# Project_Milestone04_v3_0_0.net
KiCad netlist of a schematic drawn in EAGLE
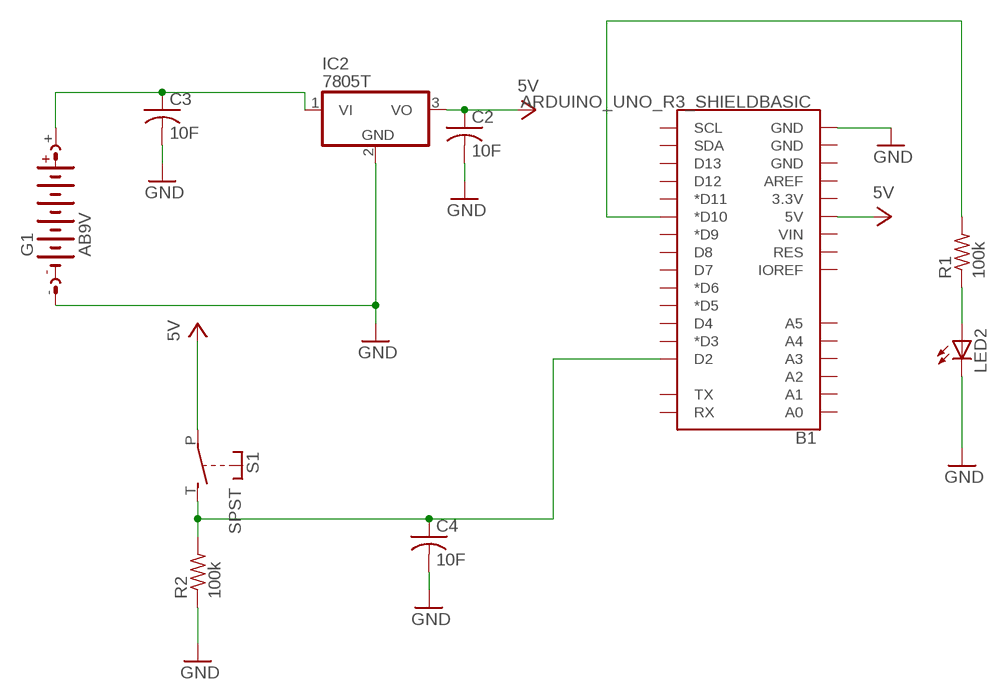
[diagram p0: schematic, sheet 1]

(export (version "E")
  (design (tool "Eeschema 10.0.6"))
  (components
    (comp (ref "B1")
      (value "ARDUINO_UNO_R3_SHIELDBASIC")
      (footprint "eagle-import:UNO_R3_SHIELD")
      (libsource (lib "eagle-import") (part "ARDUINO_UNO_R3_SHIELDBASIC"))
    )
    (comp (ref "C2")
      (value "10F")
      (footprint "eagle-import:C0805")
      (libsource (lib "eagle-import") (part "C-USC0805"))
    )
    (comp (ref "C3")
      (value "10F")
      (footprint "eagle-import:C0805")
      (libsource (lib "eagle-import") (part "C-USC0805"))
    )
    (comp (ref "C4")
      (value "10F")
      (footprint "eagle-import:C0805")
      (libsource (lib "eagle-import") (part "C-USC0805"))
    )
    (comp (ref "G1")
      (value "AB9V")
      (footprint "eagle-import:AB9V")
      (libsource (lib "eagle-import") (part "AB9V"))
    )
    (comp (ref "IC2")
      (value "7805T")
      (footprint "eagle-import:TO220H")
      (libsource (lib "eagle-import") (part "78T05"))
    )
    (comp (ref "LED2")
      (value "LED5MM")
      (footprint "eagle-import:LED5MM")
      (libsource (lib "eagle-import") (part "LED5MM"))
    )
    (comp (ref "R1")
      (value "100k")
      (footprint "eagle-import:0207_10")
      (libsource (lib "eagle-import") (part "R-US_0207/10"))
    )
    (comp (ref "R2")
      (value "100k")
      (footprint "eagle-import:0207_10")
      (libsource (lib "eagle-import") (part "R-US_0207/10"))
    )
    (comp (ref "S1")
      (value "SPST")
      (footprint "eagle-import:JUDCOSPST")
      (libsource (lib "eagle-import") (part "SPST"))
    )
  )
  (nets
    (net (code "1") (name "5V") (class "Default")
      (node (ref "B1") (pin "5V") (pinfunction "5V_5V") (pintype "bidirectional"))
      (node (ref "C2") (pin "1") (pinfunction "1_1") (pintype "passive"))
      (node (ref "IC2") (pin "3") (pinfunction "VO_3") (pintype "passive"))
      (node (ref "S1") (pin "P") (pinfunction "P_P") (pintype "passive"))
    )
    (net (code "2") (name "GND") (class "Default")
      (node (ref "B1") (pin "GND@0") (pinfunction "GND_GND@0") (pintype "bidirectional"))
      (node (ref "C2") (pin "2") (pinfunction "2_2") (pintype "passive"))
      (node (ref "C3") (pin "2") (pinfunction "2_2") (pintype "passive"))
      (node (ref "C4") (pin "2") (pinfunction "2_2") (pintype "passive"))
      (node (ref "G1") (pin "-") (pinfunction "-_-") (pintype "passive"))
      (node (ref "IC2") (pin "2") (pinfunction "GND_2") (pintype "passive"))
      (node (ref "LED2") (pin "K") (pinfunction "C_K") (pintype "passive"))
      (node (ref "R2") (pin "1") (pinfunction "1_1") (pintype "passive"))
    )
    (net (code "3") (name "Net-(B1-*D10)") (class "Default")
      (node (ref "B1") (pin "D10") (pinfunction "*D10_D10") (pintype "bidirectional"))
      (node (ref "R1") (pin "2") (pinfunction "2_2") (pintype "passive"))
    )
    (net (code "4") (name "Net-(IC2-VI)") (class "Default")
      (node (ref "C3") (pin "1") (pinfunction "1_1") (pintype "passive"))
      (node (ref "G1") (pin "+") (pinfunction "+_+") (pintype "passive"))
      (node (ref "IC2") (pin "1") (pinfunction "VI_1") (pintype "input"))
    )
    (net (code "5") (name "Net-(LED2-PadA)") (class "Default")
      (node (ref "LED2") (pin "A") (pinfunction "A_A") (pintype "passive"))
      (node (ref "R1") (pin "1") (pinfunction "1_1") (pintype "passive"))
    )
    (net (code "6") (name "Net-(S1-S)") (class "Default")
      (node (ref "B1") (pin "D2") (pinfunction "D2_D2") (pintype "bidirectional"))
      (node (ref "C4") (pin "1") (pinfunction "1_1") (pintype "passive"))
      (node (ref "R2") (pin "2") (pinfunction "2_2") (pintype "passive"))
      (node (ref "S1") (pin "T") (pinfunction "S_T") (pintype "passive"))
    )
    (net (code "7") (name "unconnected-(B1-*D3-PadD3)") (class "Default")
      (node (ref "B1") (pin "D3") (pinfunction "*D3_D3") (pintype "bidirectional"))
    )
    (net (code "8") (name "unconnected-(B1-*D5-PadD5)") (class "Default")
      (node (ref "B1") (pin "D5") (pinfunction "*D5_D5") (pintype "bidirectional"))
    )
    (net (code "9") (name "unconnected-(B1-*D6-PadD6)") (class "Default")
      (node (ref "B1") (pin "D6") (pinfunction "*D6_D6") (pintype "bidirectional"))
    )
    (net (code "10") (name "unconnected-(B1-*D9-PadD9)") (class "Default")
      (node (ref "B1") (pin "D9") (pinfunction "*D9_D9") (pintype "bidirectional"))
    )
    (net (code "11") (name "unconnected-(B1-*D11-PadD11)") (class "Default")
      (node (ref "B1") (pin "D11") (pinfunction "*D11_D11") (pintype "bidirectional"))
    )
    (net (code "12") (name "unconnected-(B1-GND-PadGND@1)") (class "Default")
      (node (ref "B1") (pin "GND@1") (pinfunction "GND_GND@1") (pintype "bidirectional"))
    )
    (net (code "13") (name "unconnected-(B1-GND-PadGND@2)") (class "Default")
      (node (ref "B1") (pin "GND@2") (pinfunction "GND_GND@2") (pintype "bidirectional"))
    )
    (net (code "14") (name "unconnected-(B1-Pad3.3V)") (class "Default")
      (node (ref "B1") (pin "3.3V") (pinfunction "3.3V_3.3V") (pintype "bidirectional"))
    )
    (net (code "15") (name "unconnected-(B1-PadA0)") (class "Default")
      (node (ref "B1") (pin "A0") (pinfunction "A0_A0") (pintype "bidirectional"))
    )
    (net (code "16") (name "unconnected-(B1-PadA1)") (class "Default")
      (node (ref "B1") (pin "A1") (pinfunction "A1_A1") (pintype "bidirectional"))
    )
    (net (code "17") (name "unconnected-(B1-PadA2)") (class "Default")
      (node (ref "B1") (pin "A2") (pinfunction "A2_A2") (pintype "bidirectional"))
    )
    (net (code "18") (name "unconnected-(B1-PadA3)") (class "Default")
      (node (ref "B1") (pin "A3") (pinfunction "A3_A3") (pintype "bidirectional"))
    )
    (net (code "19") (name "unconnected-(B1-PadA4)") (class "Default")
      (node (ref "B1") (pin "A4") (pinfunction "A4_A4") (pintype "bidirectional"))
    )
    (net (code "20") (name "unconnected-(B1-PadA5)") (class "Default")
      (node (ref "B1") (pin "A5") (pinfunction "A5_A5") (pintype "bidirectional"))
    )
    (net (code "21") (name "unconnected-(B1-PadAREF)") (class "Default")
      (node (ref "B1") (pin "AREF") (pinfunction "AREF_AREF") (pintype "bidirectional"))
    )
    (net (code "22") (name "unconnected-(B1-PadD4)") (class "Default")
      (node (ref "B1") (pin "D4") (pinfunction "D4_D4") (pintype "bidirectional"))
    )
    (net (code "23") (name "unconnected-(B1-PadD7)") (class "Default")
      (node (ref "B1") (pin "D7") (pinfunction "D7_D7") (pintype "bidirectional"))
    )
    (net (code "24") (name "unconnected-(B1-PadD8)") (class "Default")
      (node (ref "B1") (pin "D8") (pinfunction "D8_D8") (pintype "bidirectional"))
    )
    (net (code "25") (name "unconnected-(B1-PadD12)") (class "Default")
      (node (ref "B1") (pin "D12") (pinfunction "D12_D12") (pintype "bidirectional"))
    )
    (net (code "26") (name "unconnected-(B1-PadD13)") (class "Default")
      (node (ref "B1") (pin "D13") (pinfunction "D13_D13") (pintype "bidirectional"))
    )
    (net (code "27") (name "unconnected-(B1-PadIOREF)") (class "Default")
      (node (ref "B1") (pin "IOREF") (pinfunction "IOREF_IOREF") (pintype "bidirectional"))
    )
    (net (code "28") (name "unconnected-(B1-PadRES)") (class "Default")
      (node (ref "B1") (pin "RES") (pinfunction "RES_RES") (pintype "bidirectional"))
    )
    (net (code "29") (name "unconnected-(B1-PadRX)") (class "Default")
      (node (ref "B1") (pin "RX") (pinfunction "RX_RX") (pintype "bidirectional"))
    )
    (net (code "30") (name "unconnected-(B1-PadSCL)") (class "Default")
      (node (ref "B1") (pin "SCL") (pinfunction "SCL_SCL") (pintype "bidirectional"))
    )
    (net (code "31") (name "unconnected-(B1-PadSDA)") (class "Default")
      (node (ref "B1") (pin "SDA") (pinfunction "SDA_SDA") (pintype "bidirectional"))
    )
    (net (code "32") (name "unconnected-(B1-PadTX)") (class "Default")
      (node (ref "B1") (pin "TX") (pinfunction "TX_TX") (pintype "bidirectional"))
    )
    (net (code "33") (name "unconnected-(B1-PadVIN)") (class "Default")
      (node (ref "B1") (pin "VIN") (pinfunction "VIN_VIN") (pintype "bidirectional"))
    )
  )
)
